# learn_smd.net
KiCad netlist of a schematic drawn in EAGLE
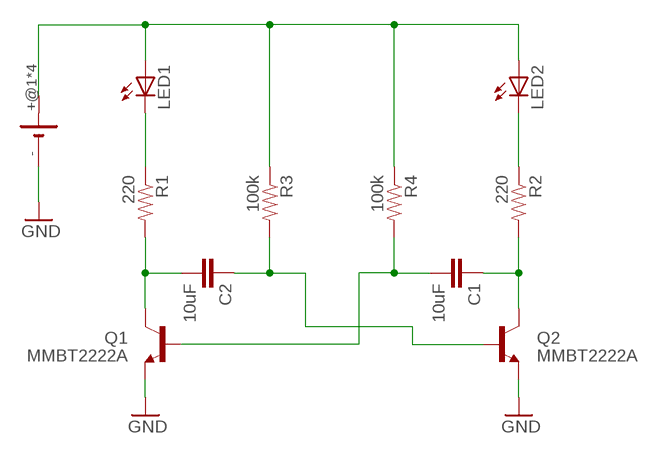
[diagram p0: schematic, sheet 1]

(export (version "E")
  (design (tool "Eeschema 10.0.6"))
  (components
    (comp (ref "BT1")
      (value "BAT-HLD-001-THM")
      (footprint "eagle-import:LINX_BAT-HLD-001-THM")
      (libsource (lib "eagle-import") (part "BAT-HLD-001-THM"))
    )
    (comp (ref "C1")
      (value "10uF")
      (footprint "eagle-import:0805")
      (libsource (lib "eagle-import") (part "CAP0805"))
    )
    (comp (ref "C2")
      (value "10uF")
      (footprint "eagle-import:0805")
      (libsource (lib "eagle-import") (part "CAP0805"))
    )
    (comp (ref "LED1")
      (value "LEDCHIP-LED0805")
      (footprint "eagle-import:CHIP-LED0805")
      (libsource (lib "eagle-import") (part "LEDCHIP-LED0805"))
    )
    (comp (ref "LED2")
      (value "LEDCHIP-LED0805")
      (footprint "eagle-import:CHIP-LED0805")
      (libsource (lib "eagle-import") (part "LEDCHIP-LED0805"))
    )
    (comp (ref "Q1")
      (value "MMBT2222A")
      (footprint "eagle-import:SOT23-3")
      (libsource (lib "eagle-import") (part "TRANSISTOR_NPNMMBT2222A"))
    )
    (comp (ref "Q2")
      (value "MMBT2222A")
      (footprint "eagle-import:SOT23-3")
      (libsource (lib "eagle-import") (part "TRANSISTOR_NPNMMBT2222A"))
    )
    (comp (ref "R1")
      (value "220")
      (footprint "eagle-import:0805")
      (libsource (lib "eagle-import") (part "RESISTOR0805-RES"))
    )
    (comp (ref "R2")
      (value "220")
      (footprint "eagle-import:0805")
      (libsource (lib "eagle-import") (part "RESISTOR0805-RES"))
    )
    (comp (ref "R3")
      (value "100k")
      (footprint "eagle-import:0805")
      (libsource (lib "eagle-import") (part "RESISTOR0805-RES"))
    )
    (comp (ref "R4")
      (value "100k")
      (footprint "eagle-import:0805")
      (libsource (lib "eagle-import") (part "RESISTOR0805-RES"))
    )
  )
  (nets
    (net (code "1") (name "GND") (class "Default")
      (node (ref "BT1") (pin "-") (pinfunction "-_-") (pintype "passive"))
      (node (ref "Q1") (pin "2") (pinfunction "E_2") (pintype "passive"))
      (node (ref "Q2") (pin "2") (pinfunction "E_2") (pintype "passive"))
    )
    (net (code "2") (name "Net-(BT1-+-Pad+@1)") (class "Default")
      (node (ref "BT1") (pin "+@1") (pinfunction "+_+@1") (pintype "passive"))
      (node (ref "BT1") (pin "+@2") (pinfunction "+_+@2") (pintype "passive"))
      (node (ref "BT1") (pin "+@3") (pinfunction "+_+@3") (pintype "passive"))
      (node (ref "BT1") (pin "+@4") (pinfunction "+_+@4") (pintype "passive"))
      (node (ref "LED1") (pin "A") (pinfunction "A_A") (pintype "passive"))
      (node (ref "LED2") (pin "A") (pinfunction "A_A") (pintype "passive"))
      (node (ref "R3") (pin "1") (pinfunction "1_1") (pintype "passive"))
      (node (ref "R4") (pin "1") (pinfunction "1_1") (pintype "passive"))
    )
    (net (code "3") (name "Net-(LED1-PadC)") (class "Default")
      (node (ref "LED1") (pin "C") (pinfunction "C_C") (pintype "passive"))
      (node (ref "R1") (pin "1") (pinfunction "1_1") (pintype "passive"))
    )
    (net (code "4") (name "Net-(LED2-PadC)") (class "Default")
      (node (ref "LED2") (pin "C") (pinfunction "C_C") (pintype "passive"))
      (node (ref "R2") (pin "1") (pinfunction "1_1") (pintype "passive"))
    )
    (net (code "5") (name "Net-(Q1-B)") (class "Default")
      (node (ref "C1") (pin "2") (pinfunction "2_2") (pintype "passive"))
      (node (ref "Q1") (pin "1") (pinfunction "B_1") (pintype "passive"))
      (node (ref "R4") (pin "2") (pinfunction "2_2") (pintype "passive"))
    )
    (net (code "6") (name "Net-(Q1-C)") (class "Default")
      (node (ref "C2") (pin "2") (pinfunction "2_2") (pintype "passive"))
      (node (ref "Q1") (pin "3") (pinfunction "C_3") (pintype "passive"))
      (node (ref "R1") (pin "2") (pinfunction "2_2") (pintype "passive"))
    )
    (net (code "7") (name "Net-(Q2-B)") (class "Default")
      (node (ref "C2") (pin "1") (pinfunction "1_1") (pintype "passive"))
      (node (ref "Q2") (pin "1") (pinfunction "B_1") (pintype "passive"))
      (node (ref "R3") (pin "2") (pinfunction "2_2") (pintype "passive"))
    )
    (net (code "8") (name "Net-(Q2-C)") (class "Default")
      (node (ref "C1") (pin "1") (pinfunction "1_1") (pintype "passive"))
      (node (ref "Q2") (pin "3") (pinfunction "C_3") (pintype "passive"))
      (node (ref "R2") (pin "2") (pinfunction "2_2") (pintype "passive"))
    )
  )
)
